# CVSummer.net
KiCad netlist of a schematic drawn in EAGLE
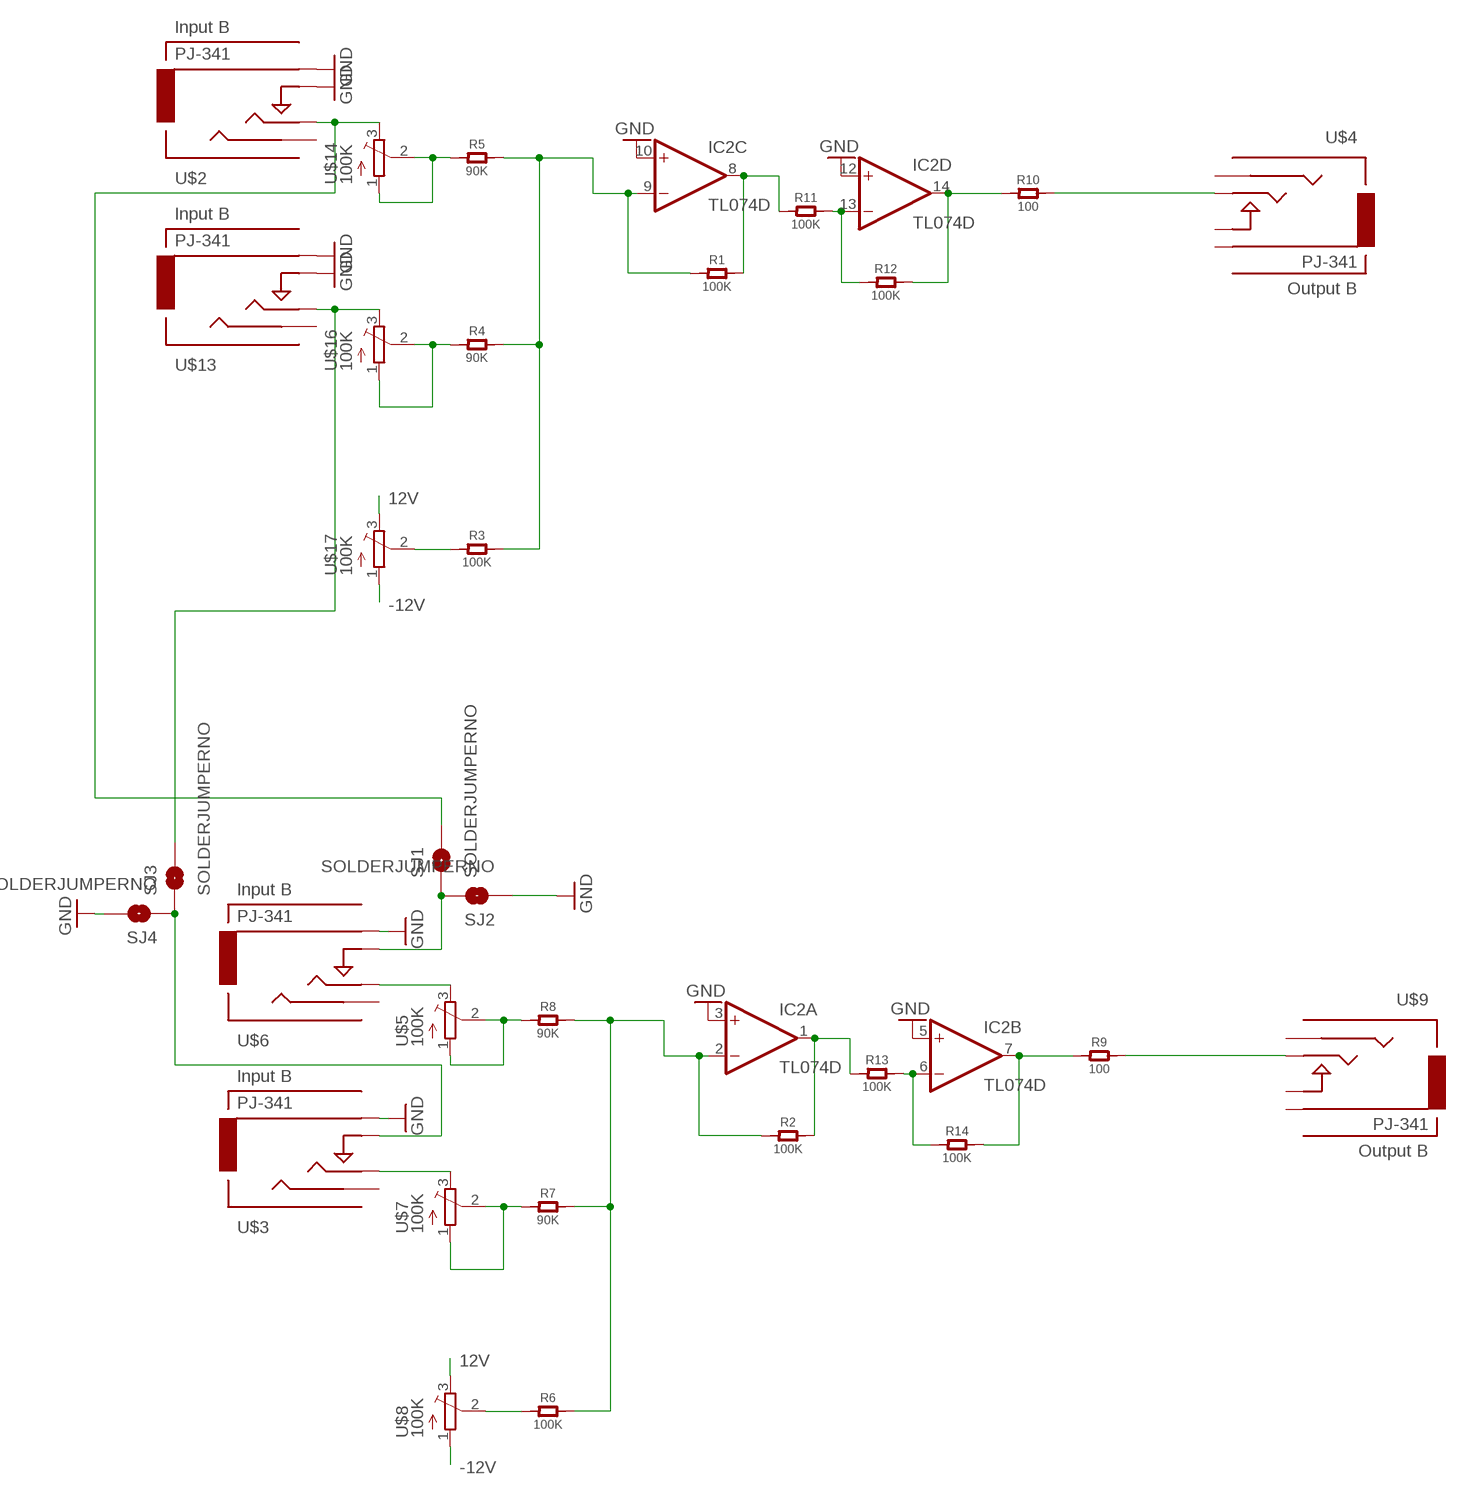
[diagram p0: schematic, sheet 1, part 1 of 2]
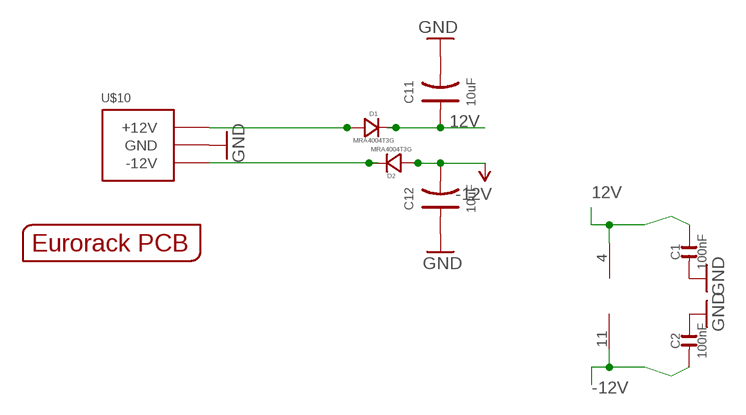
[diagram p1: schematic, sheet 1, part 2 of 2]

(export (version "E")
  (design (tool "Eeschema 10.0.6"))
  (components
    (comp (ref "C1")
      (value "100nF")
      (footprint "eagle-import:C0603")
      (libsource (lib "eagle-import") (part "C-0603"))
    )
    (comp (ref "C2")
      (value "100nF")
      (footprint "eagle-import:C0603")
      (libsource (lib "eagle-import") (part "C-0603"))
    )
    (comp (ref "C11")
      (value "10uF")
      (footprint "eagle-import:AVX-A")
      (libsource (lib "eagle-import") (part "C-POLAR-A"))
    )
    (comp (ref "C12")
      (value "10uF")
      (footprint "eagle-import:AVX-A")
      (libsource (lib "eagle-import") (part "C-POLAR-A"))
    )
    (comp (ref "D1")
      (value "MRA4004T3G")
      (footprint "eagle-import:DO-214AC")
      (fields (field (name "MF") "VISHAY") (field (name "MPN") "US1G-E3/5AT"))
      (libsource (lib "eagle-import") (part "D-SMA"))
    )
    (comp (ref "D2")
      (value "MRA4004T3G")
      (footprint "eagle-import:DO-214AC")
      (fields (field (name "MF") "VISHAY") (field (name "MPN") "US1G-E3/5AT"))
      (libsource (lib "eagle-import") (part "D-SMA"))
    )
    (comp (ref "IC2")
      (value "TL074D")
      (footprint "eagle-import:SO14")
      (libsource (lib "eagle-import") (part "TL074D"))
    )
    (comp (ref "R1")
      (value "100K")
      (footprint "eagle-import:C0805")
      (libsource (lib "eagle-import") (part "R"))
    )
    (comp (ref "R2")
      (value "100K")
      (footprint "eagle-import:C0805")
      (libsource (lib "eagle-import") (part "R"))
    )
    (comp (ref "R3")
      (value "100K")
      (footprint "eagle-import:C0805")
      (libsource (lib "eagle-import") (part "R"))
    )
    (comp (ref "R4")
      (value "90K")
      (footprint "eagle-import:C0805")
      (libsource (lib "eagle-import") (part "R"))
    )
    (comp (ref "R5")
      (value "90K")
      (footprint "eagle-import:C0805")
      (libsource (lib "eagle-import") (part "R"))
    )
    (comp (ref "R6")
      (value "100K")
      (footprint "eagle-import:C0805")
      (libsource (lib "eagle-import") (part "R"))
    )
    (comp (ref "R7")
      (value "90K")
      (footprint "eagle-import:C0805")
      (libsource (lib "eagle-import") (part "R"))
    )
    (comp (ref "R8")
      (value "90K")
      (footprint "eagle-import:C0805")
      (libsource (lib "eagle-import") (part "R"))
    )
    (comp (ref "R9")
      (value "100")
      (footprint "eagle-import:C0805")
      (libsource (lib "eagle-import") (part "R"))
    )
    (comp (ref "R10")
      (value "100")
      (footprint "eagle-import:C0805")
      (libsource (lib "eagle-import") (part "R"))
    )
    (comp (ref "R11")
      (value "100K")
      (footprint "eagle-import:C0805")
      (libsource (lib "eagle-import") (part "R"))
    )
    (comp (ref "R12")
      (value "100K")
      (footprint "eagle-import:C0805")
      (libsource (lib "eagle-import") (part "R"))
    )
    (comp (ref "R13")
      (value "100K")
      (footprint "eagle-import:C0805")
      (libsource (lib "eagle-import") (part "R"))
    )
    (comp (ref "R14")
      (value "100K")
      (footprint "eagle-import:C0805")
      (libsource (lib "eagle-import") (part "R"))
    )
    (comp (ref "SJ1")
      (value "SOLDERJUMPERNO")
      (footprint "eagle-import:SJ_2S-NO")
      (libsource (lib "eagle-import") (part "SOLDERJUMPERNO"))
    )
    (comp (ref "SJ2")
      (value "SOLDERJUMPERNO")
      (footprint "eagle-import:SJ_2S-NO")
      (libsource (lib "eagle-import") (part "SOLDERJUMPERNO"))
    )
    (comp (ref "SJ3")
      (value "SOLDERJUMPERNO")
      (footprint "eagle-import:SJ_2S-NO")
      (libsource (lib "eagle-import") (part "SOLDERJUMPERNO"))
    )
    (comp (ref "SJ4")
      (value "SOLDERJUMPERNO")
      (footprint "eagle-import:SJ_2S-NO")
      (libsource (lib "eagle-import") (part "SOLDERJUMPERNO"))
    )
    (comp (ref "U$1")
      (value "EURORACK_PCB4HP")
      (footprint "eagle-import:EURORACK4HPPCB")
      (libsource (lib "eagle-import") (part "EURORACK_PCB4HP"))
    )
    (comp (ref "U$2")
      (value "PJ-341")
      (footprint "eagle-import:3.5MM-JACK-SWITCH-13MM-INPUT")
      (fields (field (name "DESC") "Input B"))
      (libsource (lib "eagle-import") (part "AUDIO-JACKINPUT"))
    )
    (comp (ref "U$3")
      (value "PJ-341")
      (footprint "eagle-import:3.5MM-JACK-SWITCH-13MM-INPUT")
      (fields (field (name "DESC") "Input B"))
      (libsource (lib "eagle-import") (part "AUDIO-JACKINPUT"))
    )
    (comp (ref "U$4")
      (value "PJ-341")
      (footprint "eagle-import:3.5MM-JACK-SWITCH-13MM-OUTPUT")
      (fields (field (name "DESC") "Output B"))
      (libsource (lib "eagle-import") (part "AUDIO-JACKOUTPUT"))
    )
    (comp (ref "U$5")
      (value "100K")
      (footprint "eagle-import:TC33X")
      (libsource (lib "eagle-import") (part "TRIMPOTTC33X"))
    )
    (comp (ref "U$6")
      (value "PJ-341")
      (footprint "eagle-import:3.5MM-JACK-SWITCH-13MM-INPUT")
      (fields (field (name "DESC") "Input B"))
      (libsource (lib "eagle-import") (part "AUDIO-JACKINPUT"))
    )
    (comp (ref "U$7")
      (value "100K")
      (footprint "eagle-import:TC33X")
      (libsource (lib "eagle-import") (part "TRIMPOTTC33X"))
    )
    (comp (ref "U$8")
      (value "100K")
      (footprint "eagle-import:TC33X")
      (libsource (lib "eagle-import") (part "TRIMPOTTC33X"))
    )
    (comp (ref "U$9")
      (value "PJ-341")
      (footprint "eagle-import:3.5MM-JACK-SWITCH-13MM-OUTPUT")
      (fields (field (name "DESC") "Output B"))
      (libsource (lib "eagle-import") (part "AUDIO-JACKOUTPUT"))
    )
    (comp (ref "U$10")
      (value "POWER_SIMPLE10")
      (footprint "eagle-import:POWER_10")
      (libsource (lib "eagle-import") (part "POWER_SIMPLE10"))
    )
    (comp (ref "U$13")
      (value "PJ-341")
      (footprint "eagle-import:3.5MM-JACK-SWITCH-13MM-INPUT")
      (fields (field (name "DESC") "Input B"))
      (libsource (lib "eagle-import") (part "AUDIO-JACKINPUT"))
    )
    (comp (ref "U$14")
      (value "100K")
      (footprint "eagle-import:TC33X")
      (libsource (lib "eagle-import") (part "TRIMPOTTC33X"))
    )
    (comp (ref "U$16")
      (value "100K")
      (footprint "eagle-import:TC33X")
      (libsource (lib "eagle-import") (part "TRIMPOTTC33X"))
    )
    (comp (ref "U$17")
      (value "100K")
      (footprint "eagle-import:TC33X")
      (libsource (lib "eagle-import") (part "TRIMPOTTC33X"))
    )
  )
  (nets
    (net (code "1") (name "-12V") (class "Default")
      (node (ref "C12") (pin "-") (pinfunction "2_-") (pintype "bidirectional"))
      (node (ref "C2") (pin "1") (pinfunction "1_1") (pintype "bidirectional"))
      (node (ref "D2") (pin "1") (pinfunction "+_1") (pintype "passive"))
      (node (ref "IC2") (pin "11") (pinfunction "V-_11") (pintype "power_in"))
      (node (ref "U$17") (pin "1") (pinfunction "A_1") (pintype "passive"))
      (node (ref "U$8") (pin "1") (pinfunction "A_1") (pintype "passive"))
    )
    (net (code "2") (name "/12V") (class "Default")
      (node (ref "C1") (pin "2") (pinfunction "2_2") (pintype "bidirectional"))
      (node (ref "C11") (pin "+") (pinfunction "1_+") (pintype "bidirectional"))
      (node (ref "D1") (pin "2") (pinfunction "-_2") (pintype "passive"))
      (node (ref "IC2") (pin "4") (pinfunction "V+_4") (pintype "power_in"))
      (node (ref "U$17") (pin "3") (pinfunction "E_3") (pintype "passive"))
      (node (ref "U$8") (pin "3") (pinfunction "E_3") (pintype "passive"))
    )
    (net (code "3") (name "GND") (class "Default")
      (node (ref "C1") (pin "1") (pinfunction "1_1") (pintype "bidirectional"))
      (node (ref "C11") (pin "-") (pinfunction "2_-") (pintype "bidirectional"))
      (node (ref "C12") (pin "+") (pinfunction "1_+") (pintype "bidirectional"))
      (node (ref "C2") (pin "2") (pinfunction "2_2") (pintype "bidirectional"))
      (node (ref "IC2") (pin "10") (pinfunction "+IN_10") (pintype "input"))
      (node (ref "IC2") (pin "12") (pinfunction "+IN_12") (pintype "input"))
      (node (ref "IC2") (pin "3") (pinfunction "+IN_3") (pintype "input"))
      (node (ref "IC2") (pin "5") (pinfunction "+IN_5") (pintype "input"))
      (node (ref "SJ2") (pin "1") (pinfunction "1_1") (pintype "passive"))
      (node (ref "SJ4") (pin "2") (pinfunction "2_2") (pintype "passive"))
      (node (ref "U$10") (pin "3") (pinfunction "GND_3") (pintype "bidirectional"))
      (node (ref "U$10") (pin "4") (pinfunction "GND_4") (pintype "bidirectional"))
      (node (ref "U$10") (pin "5") (pinfunction "GND_5") (pintype "bidirectional"))
      (node (ref "U$10") (pin "6") (pinfunction "GND_6") (pintype "bidirectional"))
      (node (ref "U$10") (pin "7") (pinfunction "GND_7") (pintype "bidirectional"))
      (node (ref "U$10") (pin "8") (pinfunction "GND_8") (pintype "bidirectional"))
      (node (ref "U$13") (pin "RING@3") (pinfunction "RING_RING@3") (pintype "bidirectional"))
      (node (ref "U$13") (pin "SWITCH@3") (pinfunction "SWITCH_SWITCH@3") (pintype "bidirectional"))
      (node (ref "U$2") (pin "RING@3") (pinfunction "RING_RING@3") (pintype "bidirectional"))
      (node (ref "U$2") (pin "SWITCH@3") (pinfunction "SWITCH_SWITCH@3") (pintype "bidirectional"))
      (node (ref "U$3") (pin "RING@3") (pinfunction "RING_RING@3") (pintype "bidirectional"))
      (node (ref "U$6") (pin "RING@3") (pinfunction "RING_RING@3") (pintype "bidirectional"))
    )
    (net (code "4") (name "Net-(D1-+)") (class "Default")
      (node (ref "D1") (pin "1") (pinfunction "+_1") (pintype "passive"))
      (node (ref "U$10") (pin "10") (pinfunction "+12V_10") (pintype "bidirectional"))
      (node (ref "U$10") (pin "9") (pinfunction "+12V_9") (pintype "bidirectional"))
    )
    (net (code "5") (name "Net-(D2--)") (class "Default")
      (node (ref "D2") (pin "2") (pinfunction "-_2") (pintype "passive"))
      (node (ref "U$10") (pin "1") (pinfunction "-12V_1") (pintype "bidirectional"))
      (node (ref "U$10") (pin "2") (pinfunction "-12V_2") (pintype "bidirectional"))
    )
    (net (code "6") (name "Net-(IC2A--IN)") (class "Default")
      (node (ref "IC2") (pin "2") (pinfunction "-IN_2") (pintype "input"))
      (node (ref "R2") (pin "1") (pinfunction "1_1") (pintype "bidirectional"))
      (node (ref "R6") (pin "2") (pinfunction "2_2") (pintype "bidirectional"))
      (node (ref "R7") (pin "2") (pinfunction "2_2") (pintype "bidirectional"))
      (node (ref "R8") (pin "2") (pinfunction "2_2") (pintype "bidirectional"))
    )
    (net (code "7") (name "Net-(IC2A-OUT)") (class "Default")
      (node (ref "IC2") (pin "1") (pinfunction "OUT_1") (pintype "output"))
      (node (ref "R13") (pin "1") (pinfunction "1_1") (pintype "bidirectional"))
      (node (ref "R2") (pin "2") (pinfunction "2_2") (pintype "bidirectional"))
    )
    (net (code "8") (name "Net-(IC2B--IN)") (class "Default")
      (node (ref "IC2") (pin "6") (pinfunction "-IN_6") (pintype "input"))
      (node (ref "R13") (pin "2") (pinfunction "2_2") (pintype "bidirectional"))
      (node (ref "R14") (pin "1") (pinfunction "1_1") (pintype "bidirectional"))
    )
    (net (code "9") (name "Net-(IC2B-OUT)") (class "Default")
      (node (ref "IC2") (pin "7") (pinfunction "OUT_7") (pintype "output"))
      (node (ref "R14") (pin "2") (pinfunction "2_2") (pintype "bidirectional"))
      (node (ref "R9") (pin "1") (pinfunction "1_1") (pintype "bidirectional"))
    )
    (net (code "10") (name "Net-(IC2C--IN)") (class "Default")
      (node (ref "IC2") (pin "9") (pinfunction "-IN_9") (pintype "input"))
      (node (ref "R1") (pin "1") (pinfunction "1_1") (pintype "bidirectional"))
      (node (ref "R3") (pin "2") (pinfunction "2_2") (pintype "bidirectional"))
      (node (ref "R4") (pin "2") (pinfunction "2_2") (pintype "bidirectional"))
      (node (ref "R5") (pin "2") (pinfunction "2_2") (pintype "bidirectional"))
    )
    (net (code "11") (name "Net-(IC2C-OUT)") (class "Default")
      (node (ref "IC2") (pin "8") (pinfunction "OUT_8") (pintype "output"))
      (node (ref "R1") (pin "2") (pinfunction "2_2") (pintype "bidirectional"))
      (node (ref "R11") (pin "1") (pinfunction "1_1") (pintype "bidirectional"))
    )
    (net (code "12") (name "Net-(IC2D--IN)") (class "Default")
      (node (ref "IC2") (pin "13") (pinfunction "-IN_13") (pintype "input"))
      (node (ref "R11") (pin "2") (pinfunction "2_2") (pintype "bidirectional"))
      (node (ref "R12") (pin "1") (pinfunction "1_1") (pintype "bidirectional"))
    )
    (net (code "13") (name "Net-(IC2D-OUT)") (class "Default")
      (node (ref "IC2") (pin "14") (pinfunction "OUT_14") (pintype "output"))
      (node (ref "R10") (pin "1") (pinfunction "1_1") (pintype "bidirectional"))
      (node (ref "R12") (pin "2") (pinfunction "2_2") (pintype "bidirectional"))
    )
    (net (code "14") (name "Net-(U$3-SWITCH)") (class "Default")
      (node (ref "SJ3") (pin "1") (pinfunction "1_1") (pintype "passive"))
      (node (ref "SJ4") (pin "1") (pinfunction "1_1") (pintype "passive"))
      (node (ref "U$3") (pin "SWITCH@3") (pinfunction "SWITCH_SWITCH@3") (pintype "bidirectional"))
    )
    (net (code "15") (name "Net-(U$3-TIP)") (class "Default")
      (node (ref "U$3") (pin "TIP@3") (pinfunction "TIP_TIP@3") (pintype "bidirectional"))
      (node (ref "U$7") (pin "3") (pinfunction "E_3") (pintype "passive"))
    )
    (net (code "16") (name "Net-(U$4-TIP)") (class "Default")
      (node (ref "R10") (pin "2") (pinfunction "2_2") (pintype "bidirectional"))
      (node (ref "U$4") (pin "TIP@3") (pinfunction "TIP_TIP@3") (pintype "bidirectional"))
    )
    (net (code "17") (name "Net-(U$5-A)") (class "Default")
      (node (ref "R8") (pin "1") (pinfunction "1_1") (pintype "bidirectional"))
      (node (ref "U$5") (pin "1") (pinfunction "A_1") (pintype "passive"))
      (node (ref "U$5") (pin "2") (pinfunction "S_2") (pintype "passive"))
    )
    (net (code "18") (name "Net-(U$5-E)") (class "Default")
      (node (ref "U$5") (pin "3") (pinfunction "E_3") (pintype "passive"))
      (node (ref "U$6") (pin "TIP@3") (pinfunction "TIP_TIP@3") (pintype "bidirectional"))
    )
    (net (code "19") (name "Net-(U$6-SWITCH)") (class "Default")
      (node (ref "SJ1") (pin "1") (pinfunction "1_1") (pintype "passive"))
      (node (ref "SJ2") (pin "2") (pinfunction "2_2") (pintype "passive"))
      (node (ref "U$6") (pin "SWITCH@3") (pinfunction "SWITCH_SWITCH@3") (pintype "bidirectional"))
    )
    (net (code "20") (name "Net-(U$7-A)") (class "Default")
      (node (ref "R7") (pin "1") (pinfunction "1_1") (pintype "bidirectional"))
      (node (ref "U$7") (pin "1") (pinfunction "A_1") (pintype "passive"))
      (node (ref "U$7") (pin "2") (pinfunction "S_2") (pintype "passive"))
    )
    (net (code "21") (name "Net-(U$8-S)") (class "Default")
      (node (ref "R6") (pin "1") (pinfunction "1_1") (pintype "bidirectional"))
      (node (ref "U$8") (pin "2") (pinfunction "S_2") (pintype "passive"))
    )
    (net (code "22") (name "Net-(U$9-TIP)") (class "Default")
      (node (ref "R9") (pin "2") (pinfunction "2_2") (pintype "bidirectional"))
      (node (ref "U$9") (pin "TIP@3") (pinfunction "TIP_TIP@3") (pintype "bidirectional"))
    )
    (net (code "23") (name "Net-(U$13-TIP)") (class "Default")
      (node (ref "SJ3") (pin "2") (pinfunction "2_2") (pintype "passive"))
      (node (ref "U$13") (pin "TIP@3") (pinfunction "TIP_TIP@3") (pintype "bidirectional"))
      (node (ref "U$16") (pin "3") (pinfunction "E_3") (pintype "passive"))
    )
    (net (code "24") (name "Net-(U$14-A)") (class "Default")
      (node (ref "R5") (pin "1") (pinfunction "1_1") (pintype "bidirectional"))
      (node (ref "U$14") (pin "1") (pinfunction "A_1") (pintype "passive"))
      (node (ref "U$14") (pin "2") (pinfunction "S_2") (pintype "passive"))
    )
    (net (code "25") (name "Net-(U$14-E)") (class "Default")
      (node (ref "SJ1") (pin "2") (pinfunction "2_2") (pintype "passive"))
      (node (ref "U$14") (pin "3") (pinfunction "E_3") (pintype "passive"))
      (node (ref "U$2") (pin "TIP@3") (pinfunction "TIP_TIP@3") (pintype "bidirectional"))
    )
    (net (code "26") (name "Net-(U$16-A)") (class "Default")
      (node (ref "R4") (pin "1") (pinfunction "1_1") (pintype "bidirectional"))
      (node (ref "U$16") (pin "1") (pinfunction "A_1") (pintype "passive"))
      (node (ref "U$16") (pin "2") (pinfunction "S_2") (pintype "passive"))
    )
    (net (code "27") (name "Net-(U$17-S)") (class "Default")
      (node (ref "R3") (pin "1") (pinfunction "1_1") (pintype "bidirectional"))
      (node (ref "U$17") (pin "2") (pinfunction "S_2") (pintype "passive"))
    )
    (net (code "28") (name "unconnected-(U$2-SECOND-PadSECOND@3)") (class "Default")
      (node (ref "U$2") (pin "SECOND@3") (pinfunction "SECOND_SECOND@3") (pintype "bidirectional"))
    )
    (net (code "29") (name "unconnected-(U$3-SECOND-PadSECOND@3)") (class "Default")
      (node (ref "U$3") (pin "SECOND@3") (pinfunction "SECOND_SECOND@3") (pintype "bidirectional"))
    )
    (net (code "30") (name "unconnected-(U$4-RING-PadRING@3)") (class "Default")
      (node (ref "U$4") (pin "RING@3") (pinfunction "RING_RING@3") (pintype "bidirectional"))
    )
    (net (code "31") (name "unconnected-(U$4-SECOND-PadSECOND@3)") (class "Default")
      (node (ref "U$4") (pin "SECOND@3") (pinfunction "SECOND_SECOND@3") (pintype "bidirectional"))
    )
    (net (code "32") (name "unconnected-(U$4-SWITCH-PadSWITCH@3)") (class "Default")
      (node (ref "U$4") (pin "SWITCH@3") (pinfunction "SWITCH_SWITCH@3") (pintype "bidirectional"))
    )
    (net (code "33") (name "unconnected-(U$6-SECOND-PadSECOND@3)") (class "Default")
      (node (ref "U$6") (pin "SECOND@3") (pinfunction "SECOND_SECOND@3") (pintype "bidirectional"))
    )
    (net (code "34") (name "unconnected-(U$9-RING-PadRING@3)") (class "Default")
      (node (ref "U$9") (pin "RING@3") (pinfunction "RING_RING@3") (pintype "bidirectional"))
    )
    (net (code "35") (name "unconnected-(U$9-SECOND-PadSECOND@3)") (class "Default")
      (node (ref "U$9") (pin "SECOND@3") (pinfunction "SECOND_SECOND@3") (pintype "bidirectional"))
    )
    (net (code "36") (name "unconnected-(U$9-SWITCH-PadSWITCH@3)") (class "Default")
      (node (ref "U$9") (pin "SWITCH@3") (pinfunction "SWITCH_SWITCH@3") (pintype "bidirectional"))
    )
    (net (code "37") (name "unconnected-(U$13-SECOND-PadSECOND@3)") (class "Default")
      (node (ref "U$13") (pin "SECOND@3") (pinfunction "SECOND_SECOND@3") (pintype "bidirectional"))
    )
  )
)
